# 5V_Regulator.net
KiCad netlist of a schematic drawn in Altium Designer
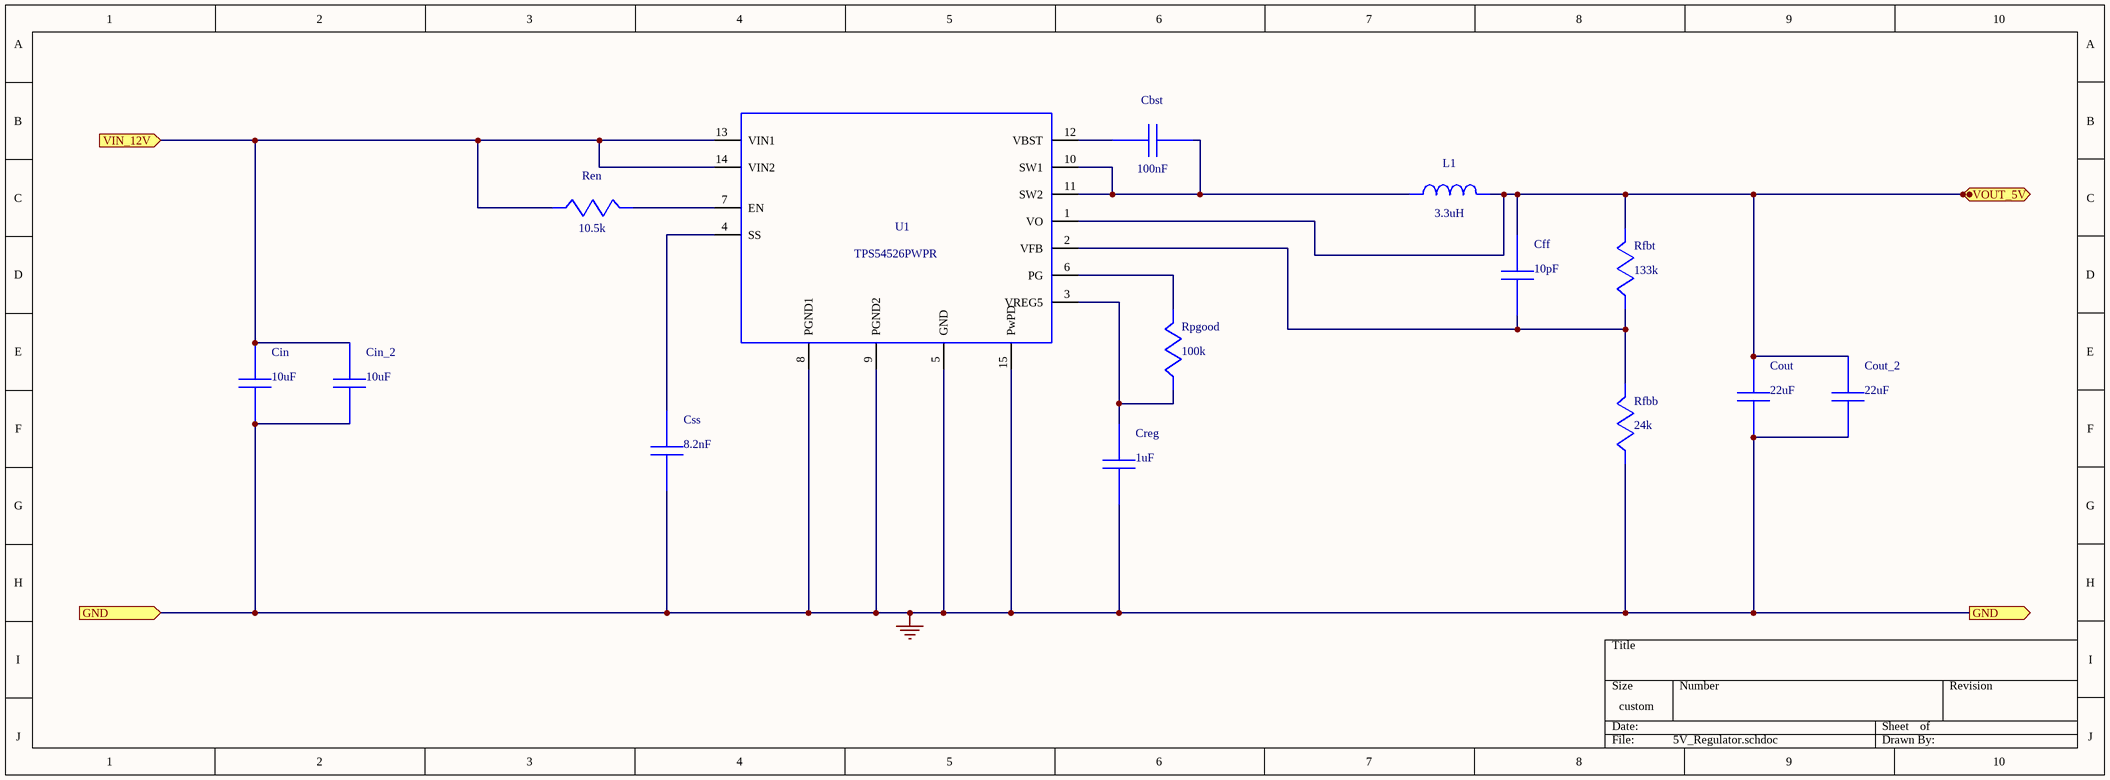
[diagram p0: 5V_Regulator.schdoc]

(export (version "E")
  (design (tool "Eeschema 10.0.6"))
  (components
    (comp (ref "Cbst")
      (value "100nF")
      (description "GRM155R61A104KA0")
      (fields (field (name "MANUFACTURER PART NUMBER") "GRM155R61A104KA01D"))
      (libsource (lib "TI WEBENCH") (part "Cbst"))
    )
    (comp (ref "Cff")
      (value "10pF")
      (description "GCM0335C1E100JD0")
      (fields (field (name "MANUFACTURER PART NUMBER") "GCM0335C1E100JD03D"))
      (libsource (lib "TI WEBENCH") (part "Cff"))
    )
    (comp (ref "Cin")
      (value "10uF")
      (description "GRM21BR61C106KE1")
      (fields (field (name "MANUFACTURER PART NUMBER") "GRM21BR61C106KE15L"))
      (libsource (lib "TI WEBENCH") (part "Cin"))
    )
    (comp (ref "Cin_2")
      (value "10uF")
      (description "GRM21BR61C106KE1")
      (fields (field (name "MANUFACTURER PART NUMBER") "GRM21BR61C106KE15L"))
      (libsource (lib "TI WEBENCH") (part "Cin_2"))
    )
    (comp (ref "Cout")
      (value "22uF")
      (description "LMK212BJ226MG-T")
      (libsource (lib "TI WEBENCH") (part "Cout"))
    )
    (comp (ref "Cout_2")
      (value "22uF")
      (description "LMK212BJ226MG-T")
      (libsource (lib "TI WEBENCH") (part "Cout_2"))
    )
    (comp (ref "Creg")
      (value "1uF")
      (description "C0603C105Z8VACTU")
      (libsource (lib "TI WEBENCH") (part "Creg"))
    )
    (comp (ref "Css")
      (value "8.2nF")
      (description "GRM033R61A822KA0")
      (fields (field (name "MANUFACTURER PART NUMBER") "GRM033R61A822KA01D"))
      (libsource (lib "TI WEBENCH") (part "Css"))
    )
    (comp (ref "L1")
      (value "3.3uH")
      (description "XAL5030-332MEB")
      (libsource (lib "TI WEBENCH") (part "L1"))
    )
    (comp (ref "Ren")
      (value "10.5k")
      (description "CRCW040210K5FKED")
      (libsource (lib "TI WEBENCH") (part "Ren"))
    )
    (comp (ref "Rfbb")
      (value "24k")
      (description "RC0603FR-0724KL")
      (libsource (lib "TI WEBENCH") (part "Rfbb"))
    )
    (comp (ref "Rfbt")
      (value "133k")
      (description "ERJ-6ENF1333V")
      (libsource (lib "TI WEBENCH") (part "Rfbt"))
    )
    (comp (ref "Rpgood")
      (value "100k")
      (description "CRCW0402100KFKED")
      (libsource (lib "TI WEBENCH") (part "Rpgood"))
    )
    (comp (ref "U1")
      (value "TPS54526PWPR")
      (fields (field (name "PACKAGEREFERENCE") "TPS54526PWPR"))
      (libsource (lib "TI WEBENCH") (part "U1"))
    )
  )
  (nets
    (net (code "1") (name "/VIN_12V") (class "Default")
      (node (ref "Cin") (pin "1") (pinfunction "1_1") (pintype "passive"))
      (node (ref "Cin_2") (pin "1") (pinfunction "1_1") (pintype "passive"))
      (node (ref "Ren") (pin "2") (pinfunction "2_2") (pintype "passive"))
      (node (ref "U1") (pin "13") (pinfunction "VIN1_13") (pintype "passive"))
      (node (ref "U1") (pin "14") (pinfunction "VIN2_14") (pintype "passive"))
    )
    (net (code "2") (name "/VOUT_5V") (class "Default")
      (node (ref "Cff") (pin "1") (pinfunction "1_1") (pintype "passive"))
      (node (ref "Cout") (pin "1") (pinfunction "1_1") (pintype "passive"))
      (node (ref "Cout_2") (pin "1") (pinfunction "1_1") (pintype "passive"))
      (node (ref "L1") (pin "2") (pinfunction "2_2") (pintype "passive"))
      (node (ref "Rfbt") (pin "1") (pinfunction "1_1") (pintype "passive"))
      (node (ref "U1") (pin "1") (pinfunction "VO_1") (pintype "passive"))
    )
    (net (code "3") (name "0") (class "Default")
      (node (ref "Cin") (pin "2") (pinfunction "2_2") (pintype "passive"))
      (node (ref "Cin_2") (pin "2") (pinfunction "2_2") (pintype "passive"))
      (node (ref "Cout") (pin "2") (pinfunction "2_2") (pintype "passive"))
      (node (ref "Cout_2") (pin "2") (pinfunction "2_2") (pintype "passive"))
      (node (ref "Creg") (pin "2") (pinfunction "2_2") (pintype "passive"))
      (node (ref "Css") (pin "2") (pinfunction "2_2") (pintype "passive"))
      (node (ref "Rfbb") (pin "2") (pinfunction "2_2") (pintype "passive"))
      (node (ref "U1") (pin "15") (pinfunction "PwPD_15") (pintype "passive"))
      (node (ref "U1") (pin "5") (pinfunction "GND_5") (pintype "passive"))
      (node (ref "U1") (pin "8") (pinfunction "PGND1_8") (pintype "passive"))
      (node (ref "U1") (pin "9") (pinfunction "PGND2_9") (pintype "passive"))
    )
    (net (code "4") (name "Net-(U1-EN)") (class "Default")
      (node (ref "Ren") (pin "1") (pinfunction "1_1") (pintype "passive"))
      (node (ref "U1") (pin "7") (pinfunction "EN_7") (pintype "passive"))
    )
    (net (code "5") (name "Net-(U1-PG)") (class "Default")
      (node (ref "Rpgood") (pin "1") (pinfunction "1_1") (pintype "passive"))
      (node (ref "U1") (pin "6") (pinfunction "PG_6") (pintype "passive"))
    )
    (net (code "6") (name "Net-(U1-SS)") (class "Default")
      (node (ref "Css") (pin "1") (pinfunction "1_1") (pintype "passive"))
      (node (ref "U1") (pin "4") (pinfunction "SS_4") (pintype "passive"))
    )
    (net (code "7") (name "Net-(U1-SW1)") (class "Default")
      (node (ref "Cbst") (pin "2") (pinfunction "2_2") (pintype "passive"))
      (node (ref "L1") (pin "1") (pinfunction "1_1") (pintype "passive"))
      (node (ref "U1") (pin "10") (pinfunction "SW1_10") (pintype "passive"))
      (node (ref "U1") (pin "11") (pinfunction "SW2_11") (pintype "passive"))
    )
    (net (code "8") (name "Net-(U1-VBST)") (class "Default")
      (node (ref "Cbst") (pin "1") (pinfunction "1_1") (pintype "passive"))
      (node (ref "U1") (pin "12") (pinfunction "VBST_12") (pintype "passive"))
    )
    (net (code "9") (name "Net-(U1-VFB)") (class "Default")
      (node (ref "Cff") (pin "2") (pinfunction "2_2") (pintype "passive"))
      (node (ref "Rfbb") (pin "1") (pinfunction "1_1") (pintype "passive"))
      (node (ref "Rfbt") (pin "2") (pinfunction "2_2") (pintype "passive"))
      (node (ref "U1") (pin "2") (pinfunction "VFB_2") (pintype "passive"))
    )
    (net (code "10") (name "Net-(U1-VREG5)") (class "Default")
      (node (ref "Creg") (pin "1") (pinfunction "1_1") (pintype "passive"))
      (node (ref "Rpgood") (pin "2") (pinfunction "2_2") (pintype "passive"))
      (node (ref "U1") (pin "3") (pinfunction "VREG5_3") (pintype "passive"))
    )
  )
)
